# DSV1-002_REV0_1_20230223.net
KiCad netlist of a schematic drawn in Altium Designer
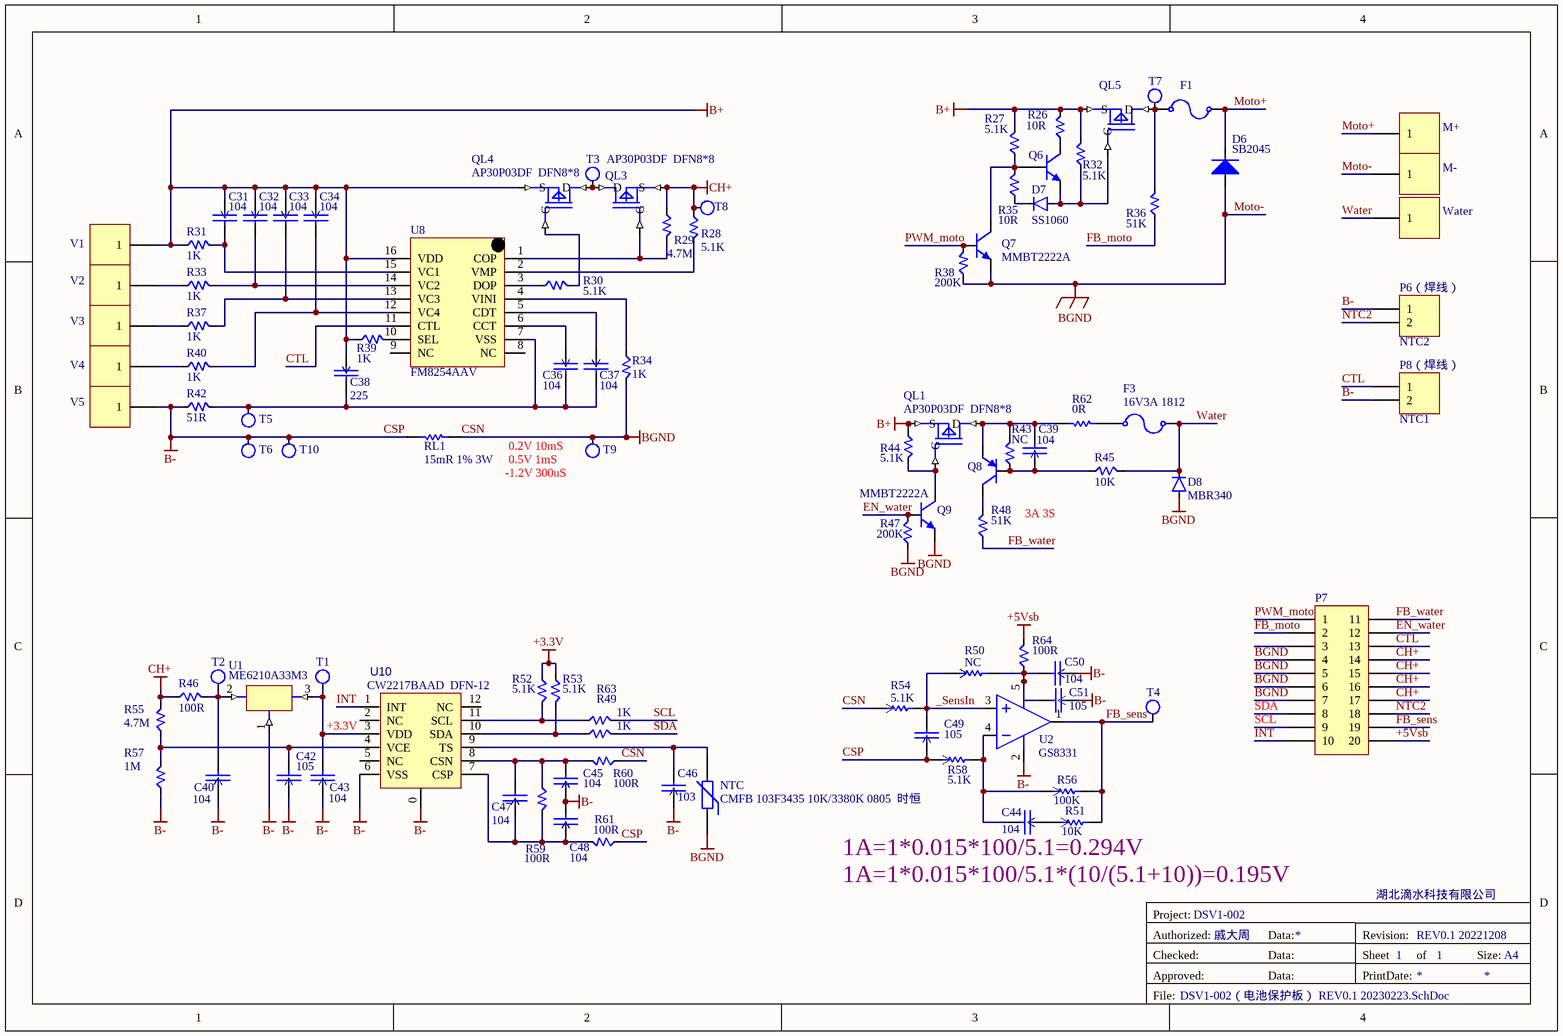
[diagram p0: DSV1-002（电池保护板） REV0.1 20230223.SchDoc]

(export (version "E")
  (design (tool "Eeschema 10.0.6"))
  (components
    (comp (ref "C31")
      (value "104")
      (footprint "0603c")
      (description "Capacitor")
      (libsource (lib "*") (part "CAP"))
    )
    (comp (ref "C32")
      (value "104")
      (footprint "0603c")
      (description "Capacitor")
      (libsource (lib "*") (part "CAP"))
    )
    (comp (ref "C33")
      (value "104")
      (footprint "0603c")
      (description "Capacitor")
      (libsource (lib "*") (part "CAP"))
    )
    (comp (ref "C34")
      (value "104")
      (footprint "0603c")
      (description "Capacitor")
      (libsource (lib "*") (part "CAP"))
    )
    (comp (ref "C36")
      (value "104")
      (footprint "0603c")
      (description "Capacitor")
      (libsource (lib "*") (part "CAP"))
    )
    (comp (ref "C37")
      (value "104")
      (footprint "0603c")
      (description "Capacitor")
      (libsource (lib "*") (part "CAP"))
    )
    (comp (ref "C38")
      (value "225")
      (footprint "0603c")
      (description "Capacitor")
      (libsource (lib "*") (part "CAP"))
    )
    (comp (ref "C39")
      (value "104")
      (footprint "0603C")
      (description "Capacitor")
      (libsource (lib "*") (part "CAP"))
    )
    (comp (ref "C40")
      (value "104")
      (footprint "0603c")
      (description "Capacitor")
      (libsource (lib "*") (part "CAP"))
    )
    (comp (ref "C42")
      (value "105")
      (footprint "0603C")
      (description "Capacitor")
      (libsource (lib "*") (part "CAP"))
    )
    (comp (ref "C43")
      (value "104")
      (footprint "0603c")
      (description "Capacitor")
      (libsource (lib "*") (part "CAP"))
    )
    (comp (ref "C44")
      (value "104")
      (footprint "0603C")
      (description "Capacitor")
      (libsource (lib "*") (part "CAP"))
    )
    (comp (ref "C45")
      (value "104")
      (footprint "0603C")
      (description "Capacitor")
      (libsource (lib "*") (part "CAP"))
    )
    (comp (ref "C46")
      (value "103")
      (footprint "0603C")
      (description "Capacitor")
      (libsource (lib "*") (part "CAP"))
    )
    (comp (ref "C47")
      (value "104")
      (footprint "0603C")
      (description "Capacitor")
      (libsource (lib "*") (part "CAP"))
    )
    (comp (ref "C48")
      (value "104")
      (footprint "0603C")
      (description "Capacitor")
      (libsource (lib "*") (part "CAP"))
    )
    (comp (ref "C49")
      (value "105")
      (footprint "0603C")
      (description "Capacitor")
      (libsource (lib "*") (part "CAP"))
    )
    (comp (ref "C50")
      (value "104")
      (footprint "0603C")
      (description "Capacitor")
      (libsource (lib "*") (part "CAP"))
    )
    (comp (ref "C51")
      (value "105")
      (footprint "0603C")
      (description "Capacitor")
      (libsource (lib "*") (part "CAP"))
    )
    (comp (ref "D6")
      (value "SB2045")
      (footprint "TO-277")
      (description "High Conductance Fast Diode")
      (libsource (lib "Miscellaneous Devices") (part "Diode 1N4448"))
    )
    (comp (ref "D7") (value "SS1060") (footprint "SOD-123") (libsource (lib "我的元件库") (part "1N4148")))
    (comp (ref "D8") (value "MBR340") (footprint "SOD-123") (libsource (lib "我的元件库") (part "1N4148")))
    (comp (ref "F1")
      (value "~")
      (footprint "1206-R")
      (description "Fuse")
      (libsource (lib "我的元件库") (part "FUSe-a"))
    )
    (comp (ref "F3")
      (value "16V3A 1812")
      (footprint "1206-R")
      (description "Fuse")
      (libsource (lib "我的元件库") (part "FUSe-a"))
    )
    (comp (ref "M+")
      (value "焊盘")
      (footprint "tp")
      (description "Header, 2-Pin")
      (libsource (lib "Miscellaneous Connectors") (part "Header 2"))
    )
    (comp (ref "M-")
      (value "焊盘")
      (footprint "tp")
      (description "Header, 2-Pin")
      (libsource (lib "Miscellaneous Connectors") (part "Header 2"))
    )
    (comp (ref "NTC")
      (value "Res Varistor")
      (footprint "6-0805")
      (description "Varistor (Voltage-Sensitive Resistor)")
      (fields (field (name "蛊秆") "CMFB 103F3435 10K/3380K 0805  时恒"))
      (libsource (lib "Miscellaneous Devices") (part "Res Varistor"))
    )
    (comp (ref "P6（焊线）")
      (value "NTC2")
      (footprint "HDR1X2")
      (description "Header, 2-Pin")
      (libsource (lib "") (part "Header 2_1"))
    )
    (comp (ref "P7")
      (value "~")
      (footprint "HDR2X10")
      (description "Header, 10-Pin, Dual row")
      (libsource (lib "Miscellaneous Connectors") (part "Header 10X2"))
    )
    (comp (ref "P8（焊线）")
      (value "NTC1")
      (footprint "HDR1X2")
      (description "Header, 2-Pin")
      (libsource (lib "") (part "Header 2_1"))
    )
    (comp (ref "Q6")
      (value "MMBT2222A")
      (footprint "SOT-23-ss")
      (description "NPN General Purpose Amplifier")
      (libsource (lib "") (part "root_0__Miscellaneous Devices.IntLib_1"))
    )
    (comp (ref "Q7")
      (value "MMBT2222A")
      (footprint "SOT-23-ss")
      (description "NPN General Purpose Amplifier")
      (libsource (lib "altium-import") (part "root_0__Miscellaneous Devices.IntLib"))
    )
    (comp (ref "Q8")
      (value "MMBT2907A")
      (footprint "SOT-23-ss")
      (description "PNP General Purpose Amplifier")
      (libsource (lib "Miscellaneous Devices") (part "2N3906"))
    )
    (comp (ref "Q9")
      (value "MMBT2222A")
      (footprint "SOT-23-ss")
      (description "NPN General Purpose Amplifier")
      (libsource (lib "Miscellaneous Devices") (part "2N3904"))
    )
    (comp (ref "QL1")
      (value "MOS-P")
      (footprint "TO-252")
      (fields (field (name "蛊秆") "AP30P03DF  DFN8*8"))
      (libsource (lib "Easen liu") (part "MOS-P"))
    )
    (comp (ref "QL3")
      (value "MOS-P")
      (footprint "TO-252")
      (fields (field (name "蛊秆") "AP30P03DF  DFN8*8"))
      (libsource (lib "Easen liu") (part "MOS-P"))
    )
    (comp (ref "QL4")
      (value "MOS-P")
      (footprint "TO-252")
      (fields (field (name "蛊秆") "AP30P03DF  DFN8*8"))
      (libsource (lib "Easen liu") (part "MOS-P"))
    )
    (comp (ref "QL5")
      (value "~")
      (footprint "TO-252")
      (description "MOS-P")
      (libsource (lib "Easen liu") (part "MOS-P"))
    )
    (comp (ref "R26") (value "10R") (footprint "0805R") (libsource (lib "*") (part "电阻 - R")))
    (comp (ref "R27") (value "5.1K") (footprint "0603R") (libsource (lib "*") (part "电阻 - R")))
    (comp (ref "R28") (value "5.1K") (footprint "0603R") (libsource (lib "*") (part "电阻 - R")))
    (comp (ref "R29") (value "4.7M") (footprint "0603R") (libsource (lib "*") (part "电阻 - R")))
    (comp (ref "R30") (value "5.1K") (footprint "0603R") (libsource (lib "*") (part "电阻 - R")))
    (comp (ref "R31") (value "1K") (footprint "0603R") (libsource (lib "*") (part "电阻 - R")))
    (comp (ref "R32") (value "5.1K") (footprint "0603R") (libsource (lib "*") (part "电阻 - R")))
    (comp (ref "R33") (value "1K") (footprint "0603R") (libsource (lib "*") (part "电阻 - R")))
    (comp (ref "R34") (value "1K") (footprint "0603R") (libsource (lib "*") (part "电阻 - R")))
    (comp (ref "R35") (value "10R") (footprint "0805R") (libsource (lib "*") (part "电阻 - R")))
    (comp (ref "R36") (value "51K") (footprint "0603R") (libsource (lib "*") (part "电阻 - R")))
    (comp (ref "R37") (value "1K") (footprint "0603R") (libsource (lib "*") (part "电阻 - R")))
    (comp (ref "R38") (value "200K") (footprint "0603R") (libsource (lib "*") (part "电阻 - R")))
    (comp (ref "R39") (value "1K") (footprint "0603R") (libsource (lib "*") (part "电阻 - R")))
    (comp (ref "R40") (value "1K") (footprint "0603R") (libsource (lib "*") (part "电阻 - R")))
    (comp (ref "R42") (value "51R") (footprint "0603R") (libsource (lib "*") (part "电阻 - R")))
    (comp (ref "R43") (value "NC") (footprint "0603R") (libsource (lib "*") (part "电阻 - R")))
    (comp (ref "R44") (value "5.1K") (footprint "0603R") (libsource (lib "*") (part "电阻 - R")))
    (comp (ref "R45") (value "10K") (footprint "0603R") (libsource (lib "*") (part "电阻 - R")))
    (comp (ref "R46") (value "100R") (footprint "0603R") (libsource (lib "*") (part "电阻 - R")))
    (comp (ref "R47") (value "200K") (footprint "0603R") (libsource (lib "*") (part "电阻 - R")))
    (comp (ref "R48") (value "51K") (footprint "0603R") (libsource (lib "*") (part "电阻 - R")))
    (comp (ref "R49") (value "1K") (footprint "0603R") (libsource (lib "*") (part "电阻 - R")))
    (comp (ref "R50") (value "NC") (footprint "0603R") (libsource (lib "*") (part "RES1")))
    (comp (ref "R51") (value "10K") (footprint "0603R") (libsource (lib "*") (part "RES1")))
    (comp (ref "R52") (value "5.1K") (footprint "0603R") (libsource (lib "*") (part "电阻 - R")))
    (comp (ref "R53") (value "5.1K") (footprint "0603R") (libsource (lib "*") (part "电阻 - R")))
    (comp (ref "R54") (value "5.1K") (footprint "0603R") (libsource (lib "*") (part "RES1")))
    (comp (ref "R55") (value "4.7M") (footprint "0603R") (libsource (lib "*") (part "电阻 - R")))
    (comp (ref "R56") (value "100K") (footprint "0603R") (libsource (lib "*") (part "RES1")))
    (comp (ref "R57") (value "1M") (footprint "0603R") (libsource (lib "*") (part "电阻 - R")))
    (comp (ref "R58") (value "5.1K") (footprint "0603R") (libsource (lib "*") (part "RES1")))
    (comp (ref "R59") (value "100R") (footprint "0603R") (libsource (lib "*") (part "电阻 - R")))
    (comp (ref "R60") (value "100R") (footprint "0603R") (libsource (lib "*") (part "电阻 - R")))
    (comp (ref "R61") (value "100R") (footprint "0603R") (libsource (lib "*") (part "电阻 - R")))
    (comp (ref "R62") (value "0R") (footprint "2512R") (libsource (lib "原理图库") (part "Res_1206/0.05R")))
    (comp (ref "R63") (value "1K") (footprint "0603R") (libsource (lib "*") (part "电阻 - R")))
    (comp (ref "R64") (value "100R") (footprint "0603R") (libsource (lib "*") (part "电阻 - R")))
    (comp (ref "RL1")
      (value "15mR 1% 3W")
      (footprint "2512R")
      (libsource (lib "原理图库") (part "Res_1206/0.05R"))
    )
    (comp (ref "T1") (value "~") (footprint "TP") (libsource (lib "*") (part "TP")))
    (comp (ref "T2") (value "~") (footprint "TP") (libsource (lib "*") (part "TP")))
    (comp (ref "T3") (value "~") (footprint "TP") (libsource (lib "*") (part "TP")))
    (comp (ref "T4") (value "~") (footprint "TP") (libsource (lib "*") (part "TP")))
    (comp (ref "T5") (value "~") (footprint "TP") (libsource (lib "*") (part "TP")))
    (comp (ref "T6") (value "~") (footprint "TP") (libsource (lib "*") (part "TP")))
    (comp (ref "T7") (value "~") (footprint "TP") (libsource (lib "*") (part "TP")))
    (comp (ref "T8") (value "~") (footprint "TP") (libsource (lib "*") (part "TP")))
    (comp (ref "T9") (value "~") (footprint "TP") (libsource (lib "*") (part "TP")))
    (comp (ref "T10") (value "~") (footprint "TP") (libsource (lib "*") (part "TP")))
    (comp (ref "U1") (value "ME6210A33M3") (footprint "SOT-23") (libsource (lib "Easen liu") (part "ME6203")))
    (comp (ref "U2") (value "GS8331") (footprint "SOT-23-5") (libsource (lib "*") (part "LMV321TP-TR")))
    (comp (ref "U8") (value "FM8254AAV") (footprint "TSSOP16") (libsource (lib "我的元件库") (part "SOP-16_1")))
    (comp (ref "U10")
      (value "~")
      (footprint "SO-8-0")
      (fields (field (name "蛊秆") "CW2217BAAD  DFN-12"))
      (libsource (lib "我的元件库") (part "IC SOT-12"))
    )
    (comp (ref "V1") (value "4*5") (footprint "4.8mm 插片端子") (libsource (lib "") (part "Header 2_2")))
    (comp (ref "V2") (value "4*4") (footprint "4.8mm 插片端子") (libsource (lib "") (part "Header 2_2")))
    (comp (ref "V3") (value "4*4") (footprint "4.8mm 插片端子") (libsource (lib "") (part "Header 2_2")))
    (comp (ref "V4") (value "4*4") (footprint "4.8mm 插片端子") (libsource (lib "*") (part "Header 2")))
    (comp (ref "V5") (value "4*5") (footprint "4.8mm 插片端子") (libsource (lib "*") (part "Header 2")))
    (comp (ref "Water")
      (value "焊盘")
      (footprint "tp")
      (description "Header, 2-Pin")
      (libsource (lib "Miscellaneous Connectors") (part "Header 2"))
    )
  )
  (nets
    (net (code "1") (name "+3.3V") (class "Default")
      (node (ref "C43") (pin "2") (pinfunction "2_2") (pintype "passive"))
      (node (ref "R52") (pin "2") (pinfunction "2_2") (pintype "passive"))
      (node (ref "R53") (pin "2") (pinfunction "2_2") (pintype "passive"))
      (node (ref "T1") (pin "1") (pinfunction "1_1") (pintype "passive"))
      (node (ref "U1") (pin "3") (pinfunction "3_3") (pintype "input"))
      (node (ref "U10") (pin "3") (pinfunction "VDD_3") (pintype "power_in"))
    )
    (net (code "2") (name "+5Vsb") (class "Default")
      (node (ref "P7") (pin "20") (pinfunction "20_20") (pintype "passive"))
      (node (ref "R64") (pin "1") (pinfunction "1_1") (pintype "passive"))
    )
    (net (code "3") (name "/CTL") (class "Default")
      (node (ref "P7") (pin "13") (pinfunction "13_13") (pintype "passive"))
      (node (ref "P8（焊线）") (pin "1") (pinfunction "1_1") (pintype "passive"))
      (node (ref "U8") (pin "11") (pinfunction "CTL_11") (pintype "passive"))
    )
    (net (code "4") (name "/EN_water") (class "Default")
      (node (ref "P7") (pin "12") (pinfunction "12_12") (pintype "passive"))
      (node (ref "Q9") (pin "1") (pinfunction "1_1") (pintype "passive"))
      (node (ref "R47") (pin "1") (pinfunction "1_1") (pintype "passive"))
    )
    (net (code "5") (name "/FB_moto") (class "Default")
      (node (ref "P7") (pin "2") (pinfunction "2_2") (pintype "passive"))
      (node (ref "R36") (pin "1") (pinfunction "1_1") (pintype "passive"))
    )
    (net (code "6") (name "/FB_sens") (class "Default")
      (node (ref "P7") (pin "19") (pinfunction "19_19") (pintype "passive"))
      (node (ref "R51") (pin "2") (pinfunction "2_2") (pintype "passive"))
      (node (ref "R56") (pin "2") (pinfunction "2_2") (pintype "passive"))
      (node (ref "T4") (pin "1") (pinfunction "1_1") (pintype "passive"))
      (node (ref "U2") (pin "1") (pinfunction "OUT_1") (pintype "passive"))
    )
    (net (code "7") (name "/FB_water") (class "Default")
      (node (ref "P7") (pin "11") (pinfunction "11_11") (pintype "passive"))
      (node (ref "R48") (pin "2") (pinfunction "2_2") (pintype "passive"))
    )
    (net (code "8") (name "/INT") (class "Default")
      (node (ref "P7") (pin "10") (pinfunction "10_10") (pintype "passive"))
      (node (ref "U10") (pin "1") (pinfunction "INT_1") (pintype "power_in"))
    )
    (net (code "9") (name "/Moto+") (class "Default")
      (node (ref "D6") (pin "2") (pinfunction "K_2") (pintype "passive"))
      (node (ref "F1") (pin "1") (pinfunction "1_1") (pintype "passive"))
      (node (ref "M+") (pin "1") (pinfunction "1_1") (pintype "passive"))
    )
    (net (code "10") (name "/NTC2") (class "Default")
      (node (ref "P6（焊线）") (pin "2") (pinfunction "2_2") (pintype "passive"))
      (node (ref "P7") (pin "18") (pinfunction "18_18") (pintype "passive"))
    )
    (net (code "11") (name "/PWM_moto") (class "Default")
      (node (ref "P7") (pin "1") (pinfunction "1_1") (pintype "passive"))
      (node (ref "Q7") (pin "1") (pinfunction "1_1") (pintype "passive"))
      (node (ref "R38") (pin "2") (pinfunction "2_2") (pintype "passive"))
    )
    (net (code "12") (name "/SCL") (class "Default")
      (node (ref "P7") (pin "9") (pinfunction "9_9") (pintype "passive"))
      (node (ref "R63") (pin "1") (pinfunction "1_1") (pintype "passive"))
    )
    (net (code "13") (name "/SDA") (class "Default")
      (node (ref "P7") (pin "8") (pinfunction "8_8") (pintype "passive"))
      (node (ref "R49") (pin "1") (pinfunction "1_1") (pintype "passive"))
    )
    (net (code "14") (name "/Water") (class "Default")
      (node (ref "D8") (pin "2") (pinfunction "2_2") (pintype "passive"))
      (node (ref "F3") (pin "1") (pinfunction "1_1") (pintype "passive"))
      (node (ref "R45") (pin "1") (pinfunction "1_1") (pintype "passive"))
      (node (ref "Water") (pin "1") (pinfunction "1_1") (pintype "passive"))
    )
    (net (code "15") (name "/_SensIn") (class "Default")
      (node (ref "C49") (pin "2") (pinfunction "2_2") (pintype "passive"))
      (node (ref "R50") (pin "1") (pinfunction "1_1") (pintype "passive"))
      (node (ref "R54") (pin "2") (pinfunction "2_2") (pintype "passive"))
      (node (ref "U2") (pin "3") (pinfunction "IN+_3") (pintype "passive"))
    )
    (net (code "16") (name "B+") (class "Default")
      (node (ref "C31") (pin "1") (pinfunction "1_1") (pintype "passive"))
      (node (ref "C32") (pin "1") (pinfunction "1_1") (pintype "passive"))
      (node (ref "C33") (pin "1") (pinfunction "1_1") (pintype "passive"))
      (node (ref "C34") (pin "1") (pinfunction "1_1") (pintype "passive"))
      (node (ref "C38") (pin "1") (pinfunction "1_1") (pintype "passive"))
      (node (ref "QL1") (pin "S") (pinfunction "S_S") (pintype "input"))
      (node (ref "QL4") (pin "S") (pinfunction "S_S") (pintype "input"))
      (node (ref "QL5") (pin "S") (pinfunction "S_S") (pintype "input"))
      (node (ref "R26") (pin "1") (pinfunction "1_1") (pintype "passive"))
      (node (ref "R27") (pin "1") (pinfunction "1_1") (pintype "passive"))
      (node (ref "R31") (pin "1") (pinfunction "1_1") (pintype "passive"))
      (node (ref "R32") (pin "1") (pinfunction "1_1") (pintype "passive"))
      (node (ref "R39") (pin "1") (pinfunction "1_1") (pintype "passive"))
      (node (ref "R44") (pin "2") (pinfunction "2_2") (pintype "passive"))
      (node (ref "U8") (pin "16") (pinfunction "VDD_16") (pintype "passive"))
      (node (ref "V1") (pin "1") (pinfunction "1_1") (pintype "passive"))
    )
    (net (code "17") (name "B-") (class "Default")
      (node (ref "C40") (pin "1") (pinfunction "1_1") (pintype "passive"))
      (node (ref "C42") (pin "1") (pinfunction "1_1") (pintype "passive"))
      (node (ref "C43") (pin "1") (pinfunction "1_1") (pintype "passive"))
      (node (ref "C45") (pin "1") (pinfunction "1_1") (pintype "passive"))
      (node (ref "C46") (pin "1") (pinfunction "1_1") (pintype "passive"))
      (node (ref "C48") (pin "2") (pinfunction "2_2") (pintype "passive"))
      (node (ref "C49") (pin "1") (pinfunction "1_1") (pintype "passive"))
      (node (ref "C50") (pin "1") (pinfunction "1_1") (pintype "passive"))
      (node (ref "C51") (pin "1") (pinfunction "1_1") (pintype "passive"))
      (node (ref "P6（焊线）") (pin "1") (pinfunction "1_1") (pintype "passive"))
      (node (ref "P8（焊线）") (pin "2") (pinfunction "2_2") (pintype "passive"))
      (node (ref "R42") (pin "1") (pinfunction "1_1") (pintype "passive"))
      (node (ref "R57") (pin "1") (pinfunction "1_1") (pintype "passive"))
      (node (ref "R58") (pin "1") (pinfunction "1_1") (pintype "passive"))
      (node (ref "R61") (pin "1") (pinfunction "1_1") (pintype "passive"))
      (node (ref "RL1") (pin "1") (pinfunction "1_1") (pintype "passive"))
      (node (ref "T10") (pin "1") (pinfunction "1_1") (pintype "passive"))
      (node (ref "T6") (pin "1") (pinfunction "1_1") (pintype "passive"))
      (node (ref "U1") (pin "1") (pinfunction "1_1") (pintype "input"))
      (node (ref "U10") (pin "0") (pintype "passive"))
      (node (ref "U10") (pin "6") (pinfunction "VSS_6") (pintype "passive"))
      (node (ref "U2") (pin "2") (pinfunction "V-_2") (pintype "passive"))
      (node (ref "V5") (pin "1") (pinfunction "1_1") (pintype "passive"))
    )
    (net (code "18") (name "BGND") (class "Default")
      (node (ref "D6") (pin "1") (pinfunction "A_1") (pintype "passive"))
      (node (ref "D8") (pin "1") (pinfunction "1_1") (pintype "passive"))
      (node (ref "M-") (pin "1") (pinfunction "1_1") (pintype "passive"))
      (node (ref "NTC") (pin "1") (pinfunction "1_1") (pintype "passive"))
      (node (ref "P7") (pin "4") (pinfunction "4_4") (pintype "passive"))
      (node (ref "P7") (pin "5") (pinfunction "5_5") (pintype "passive"))
      (node (ref "P7") (pin "6") (pinfunction "6_6") (pintype "passive"))
      (node (ref "P7") (pin "7") (pinfunction "7_7") (pintype "passive"))
      (node (ref "Q7") (pin "2") (pinfunction "2_2") (pintype "passive"))
      (node (ref "Q9") (pin "2") (pinfunction "2_2") (pintype "passive"))
      (node (ref "R34") (pin "2") (pinfunction "2_2") (pintype "passive"))
      (node (ref "R38") (pin "1") (pinfunction "1_1") (pintype "passive"))
      (node (ref "R47") (pin "2") (pinfunction "2_2") (pintype "passive"))
      (node (ref "R54") (pin "1") (pinfunction "1_1") (pintype "passive"))
      (node (ref "R60") (pin "1") (pinfunction "1_1") (pintype "passive"))
      (node (ref "RL1") (pin "2") (pinfunction "2_2") (pintype "passive"))
      (node (ref "T9") (pin "1") (pinfunction "1_1") (pintype "passive"))
    )
    (net (code "19") (name "CH+") (class "Default")
      (node (ref "P7") (pin "14") (pinfunction "14_14") (pintype "passive"))
      (node (ref "P7") (pin "15") (pinfunction "15_15") (pintype "passive"))
      (node (ref "P7") (pin "16") (pinfunction "16_16") (pintype "passive"))
      (node (ref "P7") (pin "17") (pinfunction "17_17") (pintype "passive"))
      (node (ref "QL3") (pin "S") (pinfunction "S_S") (pintype "input"))
      (node (ref "R28") (pin "1") (pinfunction "1_1") (pintype "passive"))
      (node (ref "R29") (pin "1") (pinfunction "1_1") (pintype "passive"))
      (node (ref "R46") (pin "1") (pinfunction "1_1") (pintype "passive"))
      (node (ref "R55") (pin "2") (pinfunction "2_2") (pintype "passive"))
      (node (ref "T8") (pin "1") (pinfunction "1_1") (pintype "passive"))
    )
    (net (code "20") (name "Net-(C39-Pad1)") (class "Default")
      (node (ref "C39") (pin "1") (pinfunction "1_1") (pintype "passive"))
      (node (ref "Q8") (pin "1") (pinfunction "1_1") (pintype "passive"))
      (node (ref "R43") (pin "2") (pinfunction "2_2") (pintype "passive"))
      (node (ref "R45") (pin "2") (pinfunction "2_2") (pintype "passive"))
    )
    (net (code "21") (name "Net-(C39-Pad2)") (class "Default")
      (node (ref "C39") (pin "2") (pinfunction "2_2") (pintype "passive"))
      (node (ref "Q8") (pin "2") (pinfunction "2_2") (pintype "passive"))
      (node (ref "QL1") (pin "D") (pinfunction "D_D") (pintype "input"))
      (node (ref "R43") (pin "1") (pinfunction "1_1") (pintype "passive"))
      (node (ref "R62") (pin "1") (pinfunction "1_1") (pintype "passive"))
    )
    (net (code "22") (name "Net-(C40-Pad2)") (class "Default")
      (node (ref "C40") (pin "2") (pinfunction "2_2") (pintype "passive"))
      (node (ref "R46") (pin "2") (pinfunction "2_2") (pintype "passive"))
      (node (ref "T2") (pin "1") (pinfunction "1_1") (pintype "passive"))
      (node (ref "U1") (pin "2") (pinfunction "2_2") (pintype "input"))
    )
    (net (code "23") (name "Net-(C44-Pad1)") (class "Default")
      (node (ref "C44") (pin "1") (pinfunction "1_1") (pintype "passive"))
      (node (ref "R51") (pin "1") (pinfunction "1_1") (pintype "passive"))
    )
    (net (code "24") (name "Net-(D7-Pad1)") (class "Default")
      (node (ref "D7") (pin "1") (pinfunction "1_1") (pintype "passive"))
      (node (ref "Q6") (pin "2") (pinfunction "2_2") (pintype "passive"))
      (node (ref "QL5") (pin "G") (pinfunction "G_G") (pintype "input"))
      (node (ref "R32") (pin "2") (pinfunction "2_2") (pintype "passive"))
    )
    (net (code "25") (name "Net-(D7-Pad2)") (class "Default")
      (node (ref "D7") (pin "2") (pinfunction "2_2") (pintype "passive"))
      (node (ref "R35") (pin "2") (pinfunction "2_2") (pintype "passive"))
    )
    (net (code "26") (name "Net-(F1-Pad2)") (class "Default")
      (node (ref "F1") (pin "2") (pinfunction "2_2") (pintype "passive"))
      (node (ref "QL5") (pin "D") (pinfunction "D_D") (pintype "input"))
      (node (ref "R36") (pin "2") (pinfunction "2_2") (pintype "passive"))
      (node (ref "T7") (pin "1") (pinfunction "1_1") (pintype "passive"))
    )
    (net (code "27") (name "Net-(F3-Pad2)") (class "Default")
      (node (ref "F3") (pin "2") (pinfunction "2_2") (pintype "passive"))
      (node (ref "R62") (pin "2") (pinfunction "2_2") (pintype "passive"))
    )
    (net (code "28") (name "Net-(Q6-Pad1)") (class "Default")
      (node (ref "Q6") (pin "1") (pinfunction "1_1") (pintype "passive"))
      (node (ref "Q7") (pin "3") (pinfunction "3_3") (pintype "passive"))
      (node (ref "R27") (pin "2") (pinfunction "2_2") (pintype "passive"))
      (node (ref "R35") (pin "1") (pinfunction "1_1") (pintype "passive"))
    )
    (net (code "29") (name "Net-(Q6-Pad3)") (class "Default")
      (node (ref "Q6") (pin "3") (pinfunction "3_3") (pintype "passive"))
      (node (ref "R26") (pin "2") (pinfunction "2_2") (pintype "passive"))
    )
    (net (code "30") (name "Net-(Q8-Pad3)") (class "Default")
      (node (ref "Q8") (pin "3") (pinfunction "3_3") (pintype "passive"))
      (node (ref "R48") (pin "1") (pinfunction "1_1") (pintype "passive"))
    )
    (net (code "31") (name "Net-(Q9-Pad3)") (class "Default")
      (node (ref "Q9") (pin "3") (pinfunction "3_3") (pintype "passive"))
      (node (ref "QL1") (pin "G") (pinfunction "G_G") (pintype "input"))
      (node (ref "R44") (pin "1") (pinfunction "1_1") (pintype "passive"))
    )
    (net (code "32") (name "Net-(QL3-PadD)") (class "Default")
      (node (ref "QL3") (pin "D") (pinfunction "D_D") (pintype "input"))
      (node (ref "QL4") (pin "D") (pinfunction "D_D") (pintype "input"))
      (node (ref "T3") (pin "1") (pinfunction "1_1") (pintype "passive"))
    )
    (net (code "33") (name "Net-(QL4-PadG)") (class "Default")
      (node (ref "QL4") (pin "G") (pinfunction "G_G") (pintype "input"))
      (node (ref "R30") (pin "2") (pinfunction "2_2") (pintype "passive"))
    )
    (net (code "34") (name "Net-(R33-Pad1)") (class "Default")
      (node (ref "R33") (pin "1") (pinfunction "1_1") (pintype "passive"))
      (node (ref "V2") (pin "1") (pinfunction "1_1") (pintype "passive"))
    )
    (net (code "35") (name "Net-(R37-Pad1)") (class "Default")
      (node (ref "R37") (pin "1") (pinfunction "1_1") (pintype "passive"))
      (node (ref "V3") (pin "1") (pinfunction "1_1") (pintype "passive"))
    )
    (net (code "36") (name "Net-(R40-Pad1)") (class "Default")
      (node (ref "R40") (pin "1") (pinfunction "1_1") (pintype "passive"))
      (node (ref "V4") (pin "1") (pinfunction "1_1") (pintype "passive"))
    )
    (net (code "37") (name "Net-(U2-IN-)") (class "Default")
      (node (ref "C44") (pin "2") (pinfunction "2_2") (pintype "passive"))
      (node (ref "R56") (pin "1") (pinfunction "1_1") (pintype "passive"))
      (node (ref "R58") (pin "2") (pinfunction "2_2") (pintype "passive"))
      (node (ref "U2") (pin "4") (pinfunction "IN-_4") (pintype "passive"))
    )
    (net (code "38") (name "Net-(U2-V+)") (class "Default")
      (node (ref "C50") (pin "2") (pinfunction "2_2") (pintype "passive"))
      (node (ref "C51") (pin "2") (pinfunction "2_2") (pintype "passive"))
      (node (ref "R50") (pin "2") (pinfunction "2_2") (pintype "passive"))
      (node (ref "R64") (pin "2") (pinfunction "2_2") (pintype "passive"))
      (node (ref "U2") (pin "5") (pinfunction "V+_5") (pintype "passive"))
    )
    (net (code "39") (name "Net-(U8-CCT)") (class "Default")
      (node (ref "C36") (pin "1") (pinfunction "1_1") (pintype "passive"))
      (node (ref "U8") (pin "6") (pinfunction "CCT_6") (pintype "passive"))
    )
    (net (code "40") (name "Net-(U8-CDT)") (class "Default")
      (node (ref "C37") (pin "1") (pinfunction "1_1") (pintype "passive"))
      (node (ref "U8") (pin "5") (pinfunction "CDT_5") (pintype "passive"))
    )
    (net (code "41") (name "Net-(U8-COP)") (class "Default")
      (node (ref "QL3") (pin "G") (pinfunction "G_G") (pintype "input"))
      (node (ref "R29") (pin "2") (pinfunction "2_2") (pintype "passive"))
      (node (ref "U8") (pin "1") (pinfunction "COP_1") (pintype "passive"))
    )
    (net (code "42") (name "Net-(U8-DOP)") (class "Default")
      (node (ref "R30") (pin "1") (pinfunction "1_1") (pintype "passive"))
      (node (ref "U8") (pin "3") (pinfunction "DOP_3") (pintype "passive"))
    )
    (net (code "43") (name "Net-(U8-SEL)") (class "Default")
      (node (ref "R39") (pin "2") (pinfunction "2_2") (pintype "passive"))
      (node (ref "U8") (pin "10") (pinfunction "SEL_10") (pintype "passive"))
    )
    (net (code "44") (name "Net-(U8-VC1)") (class "Default")
      (node (ref "C31") (pin "2") (pinfunction "2_2") (pintype "passive"))
      (node (ref "R31") (pin "2") (pinfunction "2_2") (pintype "passive"))
      (node (ref "U8") (pin "15") (pinfunction "VC1_15") (pintype "passive"))
    )
    (net (code "45") (name "Net-(U8-VC2)") (class "Default")
      (node (ref "C32") (pin "2") (pinfunction "2_2") (pintype "passive"))
      (node (ref "R33") (pin "2") (pinfunction "2_2") (pintype "passive"))
      (node (ref "U8") (pin "14") (pinfunction "VC2_14") (pintype "passive"))
    )
    (net (code "46") (name "Net-(U8-VC3)") (class "Default")
      (node (ref "C33") (pin "2") (pinfunction "2_2") (pintype "passive"))
      (node (ref "R37") (pin "2") (pinfunction "2_2") (pintype "passive"))
      (node (ref "U8") (pin "13") (pinfunction "VC3_13") (pintype "passive"))
    )
    (net (code "47") (name "Net-(U8-VC4)") (class "Default")
      (node (ref "C34") (pin "2") (pinfunction "2_2") (pintype "passive"))
      (node (ref "R40") (pin "2") (pinfunction "2_2") (pintype "passive"))
      (node (ref "U8") (pin "12") (pinfunction "VC4_12") (pintype "passive"))
    )
    (net (code "48") (name "Net-(U8-VINI)") (class "Default")
      (node (ref "R34") (pin "1") (pinfunction "1_1") (pintype "passive"))
      (node (ref "U8") (pin "4") (pinfunction "VINI_4") (pintype "passive"))
    )
    (net (code "49") (name "Net-(U8-VMP)") (class "Default")
      (node (ref "R28") (pin "2") (pinfunction "2_2") (pintype "passive"))
      (node (ref "U8") (pin "2") (pinfunction "VMP_2") (pintype "passive"))
    )
    (net (code "50") (name "Net-(U8-VSS)") (class "Default")
      (node (ref "C36") (pin "2") (pinfunction "2_2") (pintype "passive"))
      (node (ref "C37") (pin "2") (pinfunction "2_2") (pintype "passive"))
      (node (ref "C38") (pin "2") (pinfunction "2_2") (pintype "passive"))
      (node (ref "R42") (pin "2") (pinfunction "2_2") (pintype "passive"))
      (node (ref "T5") (pin "1") (pinfunction "1_1") (pintype "passive"))
      (node (ref "U8") (pin "7") (pinfunction "VSS_7") (pintype "passive"))
    )
    (net (code "51") (name "Net-(U10-CSN)") (class "Default")
      (node (ref "C45") (pin "2") (pinfunction "2_2") (pintype "passive"))
      (node (ref "C47") (pin "2") (pinfunction "2_2") (pintype "passive"))
      (node (ref "R59") (pin "1") (pinfunction "1_1") (pintype "passive"))
      (node (ref "R60") (pin "2") (pinfunction "2_2") (pintype "passive"))
      (node (ref "U10") (pin "8") (pinfunction "CSN_8") (pintype "passive"))
    )
    (net (code "52") (name "Net-(U10-CSP)") (class "Default")
      (node (ref "C47") (pin "1") (pinfunction "1_1") (pintype "passive"))
      (node (ref "C48") (pin "1") (pinfunction "1_1") (pintype "passive"))
      (node (ref "R59") (pin "2") (pinfunction "2_2") (pintype "passive"))
      (node (ref "R61") (pin "2") (pinfunction "2_2") (pintype "passive"))
      (node (ref "U10") (pin "7") (pinfunction "CSP_7") (pintype "passive"))
    )
    (net (code "53") (name "Net-(U10-SCL)") (class "Default")
      (node (ref "R52") (pin "1") (pinfunction "1_1") (pintype "passive"))
      (node (ref "R63") (pin "2") (pinfunction "2_2") (pintype "passive"))
      (node (ref "U10") (pin "11") (pinfunction "SCL_11") (pintype "passive"))
    )
    (net (code "54") (name "Net-(U10-SDA)") (class "Default")
      (node (ref "R49") (pin "2") (pinfunction "2_2") (pintype "passive"))
      (node (ref "R53") (pin "1") (pinfunction "1_1") (pintype "passive"))
      (node (ref "U10") (pin "10") (pinfunction "SDA_10") (pintype "passive"))
    )
    (net (code "55") (name "Net-(U10-TS)") (class "Default")
      (node (ref "C46") (pin "2") (pinfunction "2_2") (pintype "passive"))
      (node (ref "NTC") (pin "2") (pinfunction "2_2") (pintype "passive"))
      (node (ref "U10") (pin "9") (pinfunction "TS_9") (pintype "passive"))
    )
    (net (code "56") (name "Net-(U10-VCE)") (class "Default")
      (node (ref "C42") (pin "2") (pinfunction "2_2") (pintype "passive"))
      (node (ref "R55") (pin "1") (pinfunction "1_1") (pintype "passive"))
      (node (ref "R57") (pin "2") (pinfunction "2_2") (pintype "passive"))
      (node (ref "U10") (pin "4") (pinfunction "VCE_4") (pintype "passive"))
    )
    (net (code "57") (name "unconnected-(P7-Pad3)") (class "Default")
      (node (ref "P7") (pin "3") (pinfunction "3_3") (pintype "passive"))
    )
    (net (code "58") (name "unconnected-(U8-NC-Pad8)") (class "Default")
      (node (ref "U8") (pin "8") (pinfunction "NC_8") (pintype "passive"))
    )
    (net (code "59") (name "unconnected-(U8-NC-Pad9)") (class "Default")
      (node (ref "U8") (pin "9") (pinfunction "NC_9") (pintype "passive"))
    )
    (net (code "60") (name "unconnected-(U10-NC-Pad2)") (class "Default")
      (node (ref "U10") (pin "2") (pinfunction "NC_2") (pintype "power_in"))
    )
    (net (code "61") (name "unconnected-(U10-NC-Pad5)") (class "Default")
      (node (ref "U10") (pin "5") (pinfunction "NC_5") (pintype "passive"))
    )
    (net (code "62") (name "unconnected-(U10-NC-Pad12)") (class "Default")
      (node (ref "U10") (pin "12") (pinfunction "NC_12") (pintype "passive"))
    )
  )
)
